# digAudio.net
KiCad netlist of a schematic drawn in EAGLE
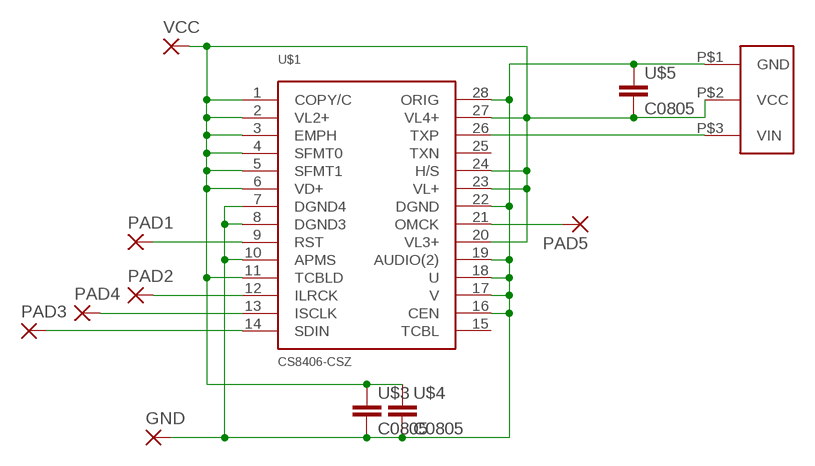
[diagram p0: schematic, sheet 1]

(export (version "E")
  (design (tool "Eeschema 10.0.6"))
  (components
    (comp (ref "GND")
      (value "SMD2")
      (footprint "eagle-import:SMD1,27-2,54")
      (libsource (lib "eagle-import") (part "SMD2"))
    )
    (comp (ref "PAD1")
      (value "SMD2")
      (footprint "eagle-import:SMD1,27-2,54")
      (libsource (lib "eagle-import") (part "SMD2"))
    )
    (comp (ref "PAD2")
      (value "SMD2")
      (footprint "eagle-import:SMD1,27-2,54")
      (libsource (lib "eagle-import") (part "SMD2"))
    )
    (comp (ref "PAD3")
      (value "SMD2")
      (footprint "eagle-import:SMD1,27-2,54")
      (libsource (lib "eagle-import") (part "SMD2"))
    )
    (comp (ref "PAD4")
      (value "SMD2")
      (footprint "eagle-import:SMD1,27-2,54")
      (libsource (lib "eagle-import") (part "SMD2"))
    )
    (comp (ref "PAD5")
      (value "SMD2")
      (footprint "eagle-import:SMD1,27-2,54")
      (libsource (lib "eagle-import") (part "SMD2"))
    )
    (comp (ref "U$1")
      (value "CS8406-CSZ")
      (footprint "eagle-import:SO28W")
      (libsource (lib "eagle-import") (part "CS8406-CSZ"))
    )
    (comp (ref "U$2")
      (value "PHOTOLINK")
      (footprint "eagle-import:PHOTOLONK")
      (libsource (lib "eagle-import") (part "PHOTOLINK"))
    )
    (comp (ref "U$3")
      (value "C0805")
      (footprint "eagle-import:Z0805")
      (libsource (lib "eagle-import") (part "C0805"))
    )
    (comp (ref "U$4")
      (value "C0805")
      (footprint "eagle-import:Z0805")
      (libsource (lib "eagle-import") (part "C0805"))
    )
    (comp (ref "U$5")
      (value "C0805")
      (footprint "eagle-import:Z0805")
      (libsource (lib "eagle-import") (part "C0805"))
    )
    (comp (ref "VCC")
      (value "SMD2")
      (footprint "eagle-import:SMD1,27-2,54")
      (libsource (lib "eagle-import") (part "SMD2"))
    )
  )
  (nets
    (net (code "1") (name "Net-(GND-P)") (class "Default")
      (node (ref "GND") (pin "1") (pinfunction "P_1") (pintype "passive"))
      (node (ref "U$1") (pin "10") (pinfunction "APMS_10") (pintype "bidirectional"))
      (node (ref "U$1") (pin "16") (pinfunction "CEN_16") (pintype "bidirectional"))
      (node (ref "U$1") (pin "17") (pinfunction "V_17") (pintype "bidirectional"))
      (node (ref "U$1") (pin "18") (pinfunction "U_18") (pintype "bidirectional"))
      (node (ref "U$1") (pin "19") (pinfunction "AUDIO(2)_19") (pintype "bidirectional"))
      (node (ref "U$1") (pin "22") (pinfunction "DGND_22") (pintype "bidirectional"))
      (node (ref "U$1") (pin "28") (pinfunction "ORIG_28") (pintype "bidirectional"))
      (node (ref "U$1") (pin "7") (pinfunction "DGND4_7") (pintype "bidirectional"))
      (node (ref "U$1") (pin "8") (pinfunction "DGND3_8") (pintype "bidirectional"))
      (node (ref "U$2") (pin "P$1") (pinfunction "GND_P$1") (pintype "bidirectional"))
      (node (ref "U$3") (pin "2") (pinfunction "2_2") (pintype "passive"))
      (node (ref "U$4") (pin "2") (pinfunction "2_2") (pintype "passive"))
      (node (ref "U$5") (pin "1") (pinfunction "1_1") (pintype "passive"))
    )
    (net (code "2") (name "Net-(PAD1-P)") (class "Default")
      (node (ref "PAD1") (pin "1") (pinfunction "P_1") (pintype "passive"))
      (node (ref "U$1") (pin "9") (pinfunction "RST_9") (pintype "bidirectional"))
    )
    (net (code "3") (name "Net-(PAD2-P)") (class "Default")
      (node (ref "PAD2") (pin "1") (pinfunction "P_1") (pintype "passive"))
      (node (ref "U$1") (pin "12") (pinfunction "ILRCK_12") (pintype "bidirectional"))
    )
    (net (code "4") (name "Net-(PAD3-P)") (class "Default")
      (node (ref "PAD3") (pin "1") (pinfunction "P_1") (pintype "passive"))
      (node (ref "U$1") (pin "14") (pinfunction "SDIN_14") (pintype "bidirectional"))
    )
    (net (code "5") (name "Net-(PAD4-P)") (class "Default")
      (node (ref "PAD4") (pin "1") (pinfunction "P_1") (pintype "passive"))
      (node (ref "U$1") (pin "13") (pinfunction "ISCLK_13") (pintype "bidirectional"))
    )
    (net (code "6") (name "Net-(PAD5-P)") (class "Default")
      (node (ref "PAD5") (pin "1") (pinfunction "P_1") (pintype "passive"))
      (node (ref "U$1") (pin "21") (pinfunction "OMCK_21") (pintype "bidirectional"))
    )
    (net (code "7") (name "Net-(U$1-COPY{slash}C)") (class "Default")
      (node (ref "U$1") (pin "1") (pinfunction "COPY/C_1") (pintype "bidirectional"))
      (node (ref "U$1") (pin "11") (pinfunction "TCBLD_11") (pintype "bidirectional"))
      (node (ref "U$1") (pin "2") (pinfunction "VL2+_2") (pintype "bidirectional"))
      (node (ref "U$1") (pin "20") (pinfunction "VL3+_20") (pintype "bidirectional"))
      (node (ref "U$1") (pin "23") (pinfunction "VL+_23") (pintype "bidirectional"))
      (node (ref "U$1") (pin "24") (pinfunction "H/S_24") (pintype "bidirectional"))
      (node (ref "U$1") (pin "27") (pinfunction "VL4+_27") (pintype "bidirectional"))
      (node (ref "U$1") (pin "3") (pinfunction "EMPH_3") (pintype "bidirectional"))
      (node (ref "U$1") (pin "4") (pinfunction "SFMT0_4") (pintype "bidirectional"))
      (node (ref "U$1") (pin "5") (pinfunction "SFMT1_5") (pintype "bidirectional"))
      (node (ref "U$1") (pin "6") (pinfunction "VD+_6") (pintype "bidirectional"))
      (node (ref "U$2") (pin "P$2") (pinfunction "VCC_P$2") (pintype "bidirectional"))
      (node (ref "U$3") (pin "1") (pinfunction "1_1") (pintype "passive"))
      (node (ref "U$4") (pin "1") (pinfunction "1_1") (pintype "passive"))
      (node (ref "U$5") (pin "2") (pinfunction "2_2") (pintype "passive"))
      (node (ref "VCC") (pin "1") (pinfunction "P_1") (pintype "passive"))
    )
    (net (code "8") (name "Net-(U$1-TXP)") (class "Default")
      (node (ref "U$1") (pin "26") (pinfunction "TXP_26") (pintype "bidirectional"))
      (node (ref "U$2") (pin "P$3") (pinfunction "VIN_P$3") (pintype "bidirectional"))
    )
    (net (code "9") (name "unconnected-(U$1-TCBL-Pad15)") (class "Default")
      (node (ref "U$1") (pin "15") (pinfunction "TCBL_15") (pintype "bidirectional"))
    )
    (net (code "10") (name "unconnected-(U$1-TXN-Pad25)") (class "Default")
      (node (ref "U$1") (pin "25") (pinfunction "TXN_25") (pintype "bidirectional"))
    )
  )
)
